# ProPrj___2026-02-20.net
KiCad netlist of a schematic drawn in EasyEDA Pro
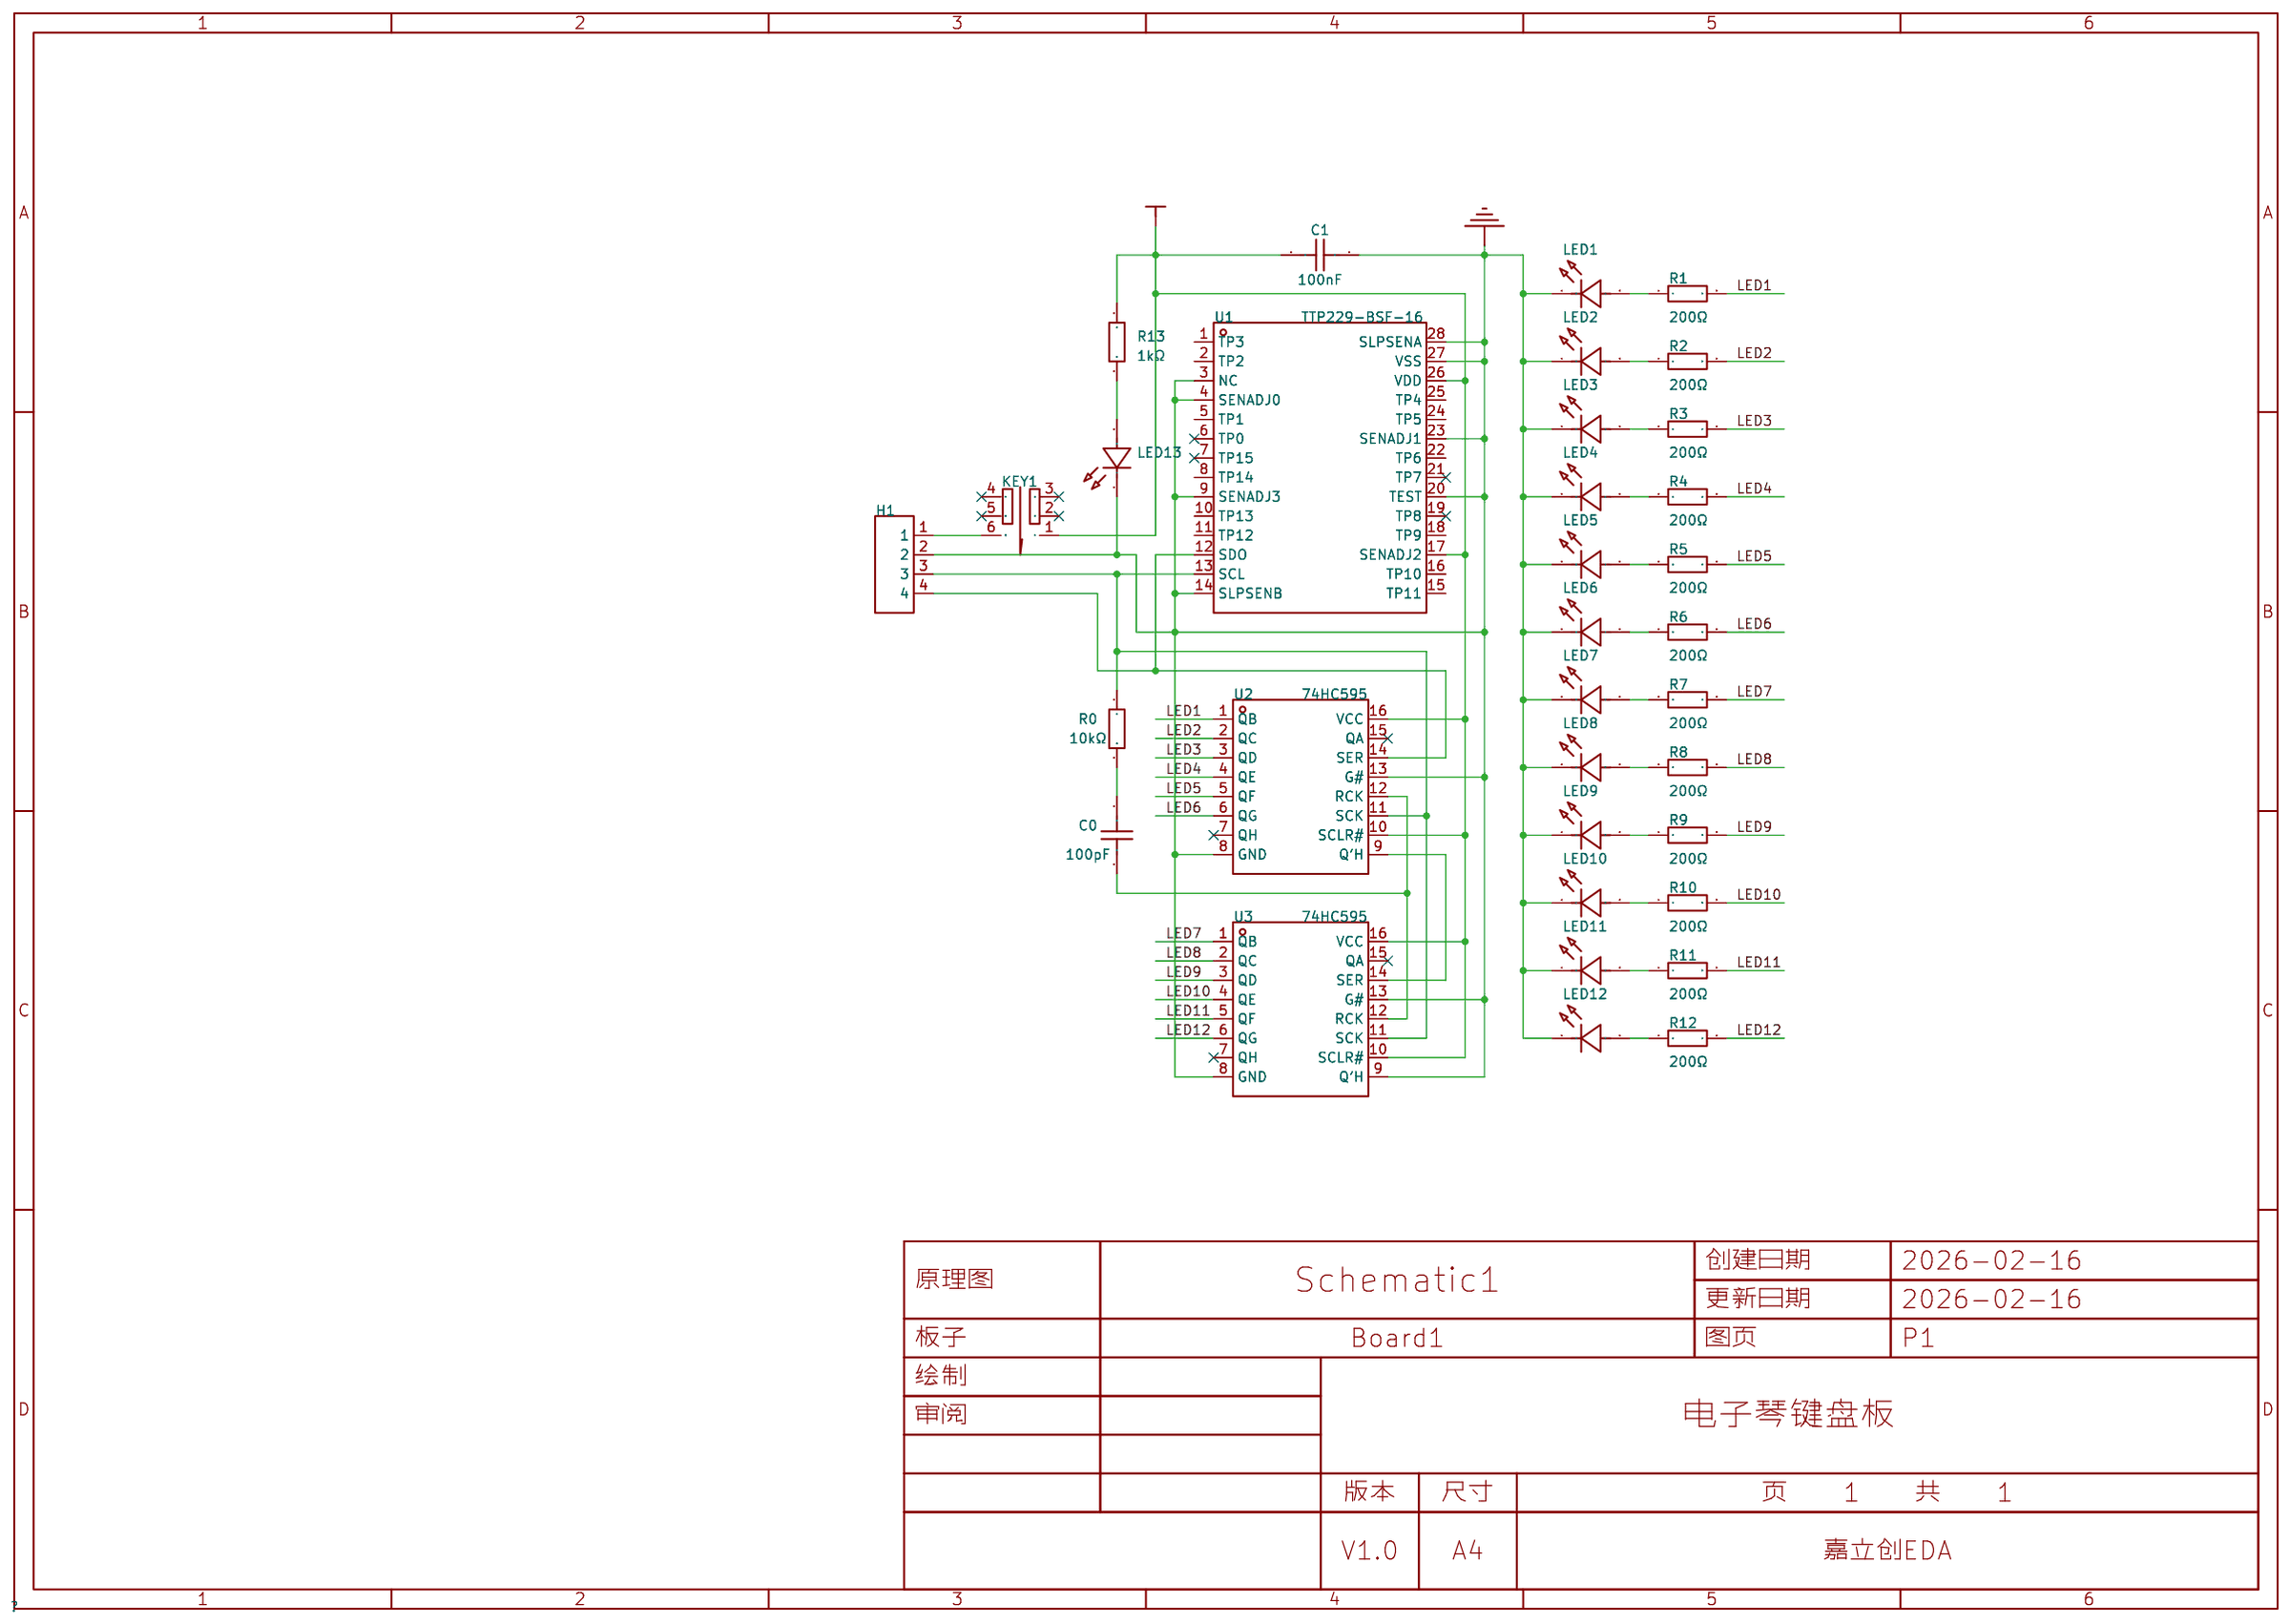
[diagram p0: schematic sheet]

(export (version "E")
  (design (tool "Eeschema 10.0.6"))
  (components
    (comp (ref "C0")
      (value "100pF")
      (footprint "easyedapro:C0603")
      (fields
        (field (name "Manufacturer Part") "CC0603JRNPO9BN101")
        (field (name "Manufacturer") "YAGEO(国巨)")
      )
      (libsource (lib "easyedapro") (part "CC0603JRNPO9BN101"))
    )
    (comp (ref "C1")
      (value "100nF")
      (footprint "easyedapro:C0603")
      (fields
        (field (name "Manufacturer Part") "CGA0603X7R104K500JT")
        (field (name "Manufacturer") "HRE(芯声)")
      )
      (libsource (lib "easyedapro") (part "CGA0603X7R104K500JT"))
    )
    (comp (ref "H1")
      (value "2.54-1*4")
      (footprint "easyedapro:HDR-TH_4P-P2.54-V-M-1")
      (fields (field (name "Manufacturer") "ZHOURI(洲日)"))
      (libsource (lib "easyedapro") (part "2.54-1*4"))
    )
    (comp (ref "KEY1")
      (value "自锁开关 5.8Z白灰白260G")
      (footprint "easyedapro:SW-TH_6P-L5.8-W5.8-P2.00-LS4.5-TR")
      (description "耐温260度")
      (libsource (lib "easyedapro") (part "Self-locking switch 5.8ZWhite and white260G"))
    )
    (comp (ref "LED1")
      (value "GL0603UB01")
      (footprint "easyedapro:LED0805-RD_GREEN")
      (fields (field (name "Manufacturer") "Guiguang light(桂光光电)"))
      (libsource (lib "easyedapro") (part "XL-2012UGC"))
    )
    (comp (ref "LED2")
      (value "GL0603UB01")
      (footprint "easyedapro:LED0805-RD_GREEN")
      (fields (field (name "Manufacturer") "Guiguang light(桂光光电)"))
      (libsource (lib "easyedapro") (part "XL-2012UGC"))
    )
    (comp (ref "LED3")
      (value "GL0603UB01")
      (footprint "easyedapro:LED0805-RD_GREEN")
      (fields (field (name "Manufacturer") "Guiguang light(桂光光电)"))
      (libsource (lib "easyedapro") (part "XL-2012UGC"))
    )
    (comp (ref "LED4")
      (value "GL0603UB01")
      (footprint "easyedapro:LED0805-RD_GREEN")
      (fields (field (name "Manufacturer") "Guiguang light(桂光光电)"))
      (libsource (lib "easyedapro") (part "XL-2012UGC"))
    )
    (comp (ref "LED5")
      (value "GL0603UB01")
      (footprint "easyedapro:LED0805-RD_GREEN")
      (fields (field (name "Manufacturer") "Guiguang light(桂光光电)"))
      (libsource (lib "easyedapro") (part "XL-2012UGC"))
    )
    (comp (ref "LED6")
      (value "GL0603UB01")
      (footprint "easyedapro:LED0805-RD_GREEN")
      (fields (field (name "Manufacturer") "Guiguang light(桂光光电)"))
      (libsource (lib "easyedapro") (part "XL-2012UGC"))
    )
    (comp (ref "LED7")
      (value "GL0603UB01")
      (footprint "easyedapro:LED0805-RD_GREEN")
      (fields (field (name "Manufacturer") "Guiguang light(桂光光电)"))
      (libsource (lib "easyedapro") (part "XL-2012UGC"))
    )
    (comp (ref "LED8")
      (value "GL0603UB01")
      (footprint "easyedapro:LED0805-RD_GREEN")
      (fields (field (name "Manufacturer") "Guiguang light(桂光光电)"))
      (libsource (lib "easyedapro") (part "XL-2012UGC"))
    )
    (comp (ref "LED9")
      (value "GL0603UB01")
      (footprint "easyedapro:LED0805-RD_GREEN")
      (fields (field (name "Manufacturer") "Guiguang light(桂光光电)"))
      (libsource (lib "easyedapro") (part "XL-2012UGC"))
    )
    (comp (ref "LED10")
      (value "GL0603UB01")
      (footprint "easyedapro:LED0805-RD_GREEN")
      (fields (field (name "Manufacturer") "Guiguang light(桂光光电)"))
      (libsource (lib "easyedapro") (part "XL-2012UGC"))
    )
    (comp (ref "LED11")
      (value "GL0603UB01")
      (footprint "easyedapro:LED0805-RD_GREEN")
      (fields (field (name "Manufacturer") "Guiguang light(桂光光电)"))
      (libsource (lib "easyedapro") (part "XL-2012UGC"))
    )
    (comp (ref "LED12")
      (value "GL0603UB01")
      (footprint "easyedapro:LED0805-RD_GREEN")
      (fields (field (name "Manufacturer") "Guiguang light(桂光光电)"))
      (libsource (lib "easyedapro") (part "XL-2012UGC"))
    )
    (comp (ref "LED13")
      (value "GL0603UB01")
      (footprint "easyedapro:LED0805-RD_GREEN")
      (fields (field (name "Manufacturer") "Guiguang light(桂光光电)"))
      (libsource (lib "easyedapro") (part "XL-2012UGC"))
    )
    (comp (ref "R0")
      (value "10kΩ")
      (footprint "easyedapro:R0805")
      (fields
        (field (name "Manufacturer Part") "0603WAF1002T5E")
        (field (name "Manufacturer") "UNI-ROYAL(厚声)")
      )
      (libsource (lib "easyedapro") (part "电阻"))
    )
    (comp (ref "R1")
      (value "200Ω")
      (footprint "easyedapro:R0805")
      (fields
        (field (name "Manufacturer Part") "0603WAF2000T5E")
        (field (name "Manufacturer") "UNI-ROYAL(厚声)")
      )
      (libsource (lib "easyedapro") (part "电阻"))
    )
    (comp (ref "R2")
      (value "200Ω")
      (footprint "easyedapro:R0805")
      (fields
        (field (name "Manufacturer Part") "0603WAF2000T5E")
        (field (name "Manufacturer") "UNI-ROYAL(厚声)")
      )
      (libsource (lib "easyedapro") (part "电阻"))
    )
    (comp (ref "R3")
      (value "200Ω")
      (footprint "easyedapro:R0805")
      (fields
        (field (name "Manufacturer Part") "0603WAF2000T5E")
        (field (name "Manufacturer") "UNI-ROYAL(厚声)")
      )
      (libsource (lib "easyedapro") (part "电阻"))
    )
    (comp (ref "R4")
      (value "200Ω")
      (footprint "easyedapro:R0805")
      (fields
        (field (name "Manufacturer Part") "0603WAF2000T5E")
        (field (name "Manufacturer") "UNI-ROYAL(厚声)")
      )
      (libsource (lib "easyedapro") (part "电阻"))
    )
    (comp (ref "R5")
      (value "200Ω")
      (footprint "easyedapro:R0805")
      (fields
        (field (name "Manufacturer Part") "0603WAF2000T5E")
        (field (name "Manufacturer") "UNI-ROYAL(厚声)")
      )
      (libsource (lib "easyedapro") (part "电阻"))
    )
    (comp (ref "R6")
      (value "200Ω")
      (footprint "easyedapro:R0805")
      (fields
        (field (name "Manufacturer Part") "0603WAF2000T5E")
        (field (name "Manufacturer") "UNI-ROYAL(厚声)")
      )
      (libsource (lib "easyedapro") (part "电阻"))
    )
    (comp (ref "R7")
      (value "200Ω")
      (footprint "easyedapro:R0805")
      (fields
        (field (name "Manufacturer Part") "0603WAF2000T5E")
        (field (name "Manufacturer") "UNI-ROYAL(厚声)")
      )
      (libsource (lib "easyedapro") (part "电阻"))
    )
    (comp (ref "R8")
      (value "200Ω")
      (footprint "easyedapro:R0805")
      (fields
        (field (name "Manufacturer Part") "0603WAF2000T5E")
        (field (name "Manufacturer") "UNI-ROYAL(厚声)")
      )
      (libsource (lib "easyedapro") (part "电阻"))
    )
    (comp (ref "R9")
      (value "200Ω")
      (footprint "easyedapro:R0805")
      (fields
        (field (name "Manufacturer Part") "0603WAF2000T5E")
        (field (name "Manufacturer") "UNI-ROYAL(厚声)")
      )
      (libsource (lib "easyedapro") (part "电阻"))
    )
    (comp (ref "R10")
      (value "200Ω")
      (footprint "easyedapro:R0805")
      (fields
        (field (name "Manufacturer Part") "0603WAF2000T5E")
        (field (name "Manufacturer") "UNI-ROYAL(厚声)")
      )
      (libsource (lib "easyedapro") (part "电阻"))
    )
    (comp (ref "R11")
      (value "200Ω")
      (footprint "easyedapro:R0805")
      (fields
        (field (name "Manufacturer Part") "0603WAF2000T5E")
        (field (name "Manufacturer") "UNI-ROYAL(厚声)")
      )
      (libsource (lib "easyedapro") (part "电阻"))
    )
    (comp (ref "R12")
      (value "200Ω")
      (footprint "easyedapro:R0805")
      (fields
        (field (name "Manufacturer Part") "0603WAF2000T5E")
        (field (name "Manufacturer") "UNI-ROYAL(厚声)")
      )
      (libsource (lib "easyedapro") (part "电阻"))
    )
    (comp (ref "R13")
      (value "1kΩ")
      (footprint "easyedapro:R0603")
      (description "电阻类型:厚膜电阻;阻值:1kΩ;精度:±1%;功率:100mW;工作电压:75V;温度系数:±100ppm/℃;")
      (fields (field (name "Manufacturer Part") "RC0603FR-071KL") (field (name "Manufacturer") "YAGEO(国巨)"))
      (libsource (lib "easyedapro") (part "RC0603FR-071KL"))
    )
    (comp (ref "U1")
      (value "TTP229-BSF-16")
      (footprint "easyedapro:SSOP-28_L9.9-W3.9-P0.64-LS6.0-BL")
      (fields (field (name "Manufacturer") "TONTEK(通泰)"))
      (libsource (lib "easyedapro") (part "TTP229-BSF-16"))
    )
    (comp (ref "U2")
      (value "74HC595")
      (footprint "easyedapro:SOP-16_L9.9-W3.9-P1.27-LS6.0-BL")
      (fields (field (name "Manufacturer") "GR(国睿)"))
      (libsource (lib "easyedapro") (part "74HC595"))
    )
    (comp (ref "U3")
      (value "74HC595")
      (footprint "easyedapro:SOP-16_L9.9-W3.9-P1.27-LS6.0-BL")
      (fields (field (name "Manufacturer") "GR(国睿)"))
      (libsource (lib "easyedapro") (part "74HC595"))
    )
  )
  (nets
    (net (code "1") (name "/LED1") (class "Default")
      (node (ref "R1") (pin "2") (pinfunction "2_2") (pintype "input"))
      (node (ref "U2") (pin "1") (pinfunction "QB_1") (pintype "unspecified"))
    )
    (net (code "2") (name "/LED2") (class "Default")
      (node (ref "R2") (pin "2") (pinfunction "2_2") (pintype "input"))
      (node (ref "U2") (pin "2") (pinfunction "QC_2") (pintype "unspecified"))
    )
    (net (code "3") (name "/LED3") (class "Default")
      (node (ref "R3") (pin "2") (pinfunction "2_2") (pintype "input"))
      (node (ref "U2") (pin "3") (pinfunction "QD_3") (pintype "unspecified"))
    )
    (net (code "4") (name "/LED4") (class "Default")
      (node (ref "R4") (pin "2") (pinfunction "2_2") (pintype "input"))
      (node (ref "U2") (pin "4") (pinfunction "QE_4") (pintype "unspecified"))
    )
    (net (code "5") (name "/LED5") (class "Default")
      (node (ref "R5") (pin "2") (pinfunction "2_2") (pintype "input"))
      (node (ref "U2") (pin "5") (pinfunction "QF_5") (pintype "unspecified"))
    )
    (net (code "6") (name "/LED6") (class "Default")
      (node (ref "R6") (pin "2") (pinfunction "2_2") (pintype "input"))
      (node (ref "U2") (pin "6") (pinfunction "QG_6") (pintype "unspecified"))
    )
    (net (code "7") (name "/LED7") (class "Default")
      (node (ref "R7") (pin "2") (pinfunction "2_2") (pintype "input"))
      (node (ref "U3") (pin "1") (pinfunction "QB_1") (pintype "unspecified"))
    )
    (net (code "8") (name "/LED8") (class "Default")
      (node (ref "R8") (pin "2") (pinfunction "2_2") (pintype "input"))
      (node (ref "U3") (pin "2") (pinfunction "QC_2") (pintype "unspecified"))
    )
    (net (code "9") (name "/LED9") (class "Default")
      (node (ref "R9") (pin "2") (pinfunction "2_2") (pintype "input"))
      (node (ref "U3") (pin "3") (pinfunction "QD_3") (pintype "unspecified"))
    )
    (net (code "10") (name "/LED10") (class "Default")
      (node (ref "R10") (pin "2") (pinfunction "2_2") (pintype "input"))
      (node (ref "U3") (pin "4") (pinfunction "QE_4") (pintype "unspecified"))
    )
    (net (code "11") (name "/LED11") (class "Default")
      (node (ref "R11") (pin "2") (pinfunction "2_2") (pintype "input"))
      (node (ref "U3") (pin "5") (pinfunction "QF_5") (pintype "unspecified"))
    )
    (net (code "12") (name "/LED12") (class "Default")
      (node (ref "R12") (pin "2") (pinfunction "2_2") (pintype "input"))
      (node (ref "U3") (pin "6") (pinfunction "QG_6") (pintype "unspecified"))
    )
    (net (code "13") (name "GND") (class "Default")
      (node (ref "C1") (pin "1") (pinfunction "1_1") (pintype "unspecified"))
      (node (ref "H1") (pin "2") (pinfunction "2_2") (pintype "unspecified"))
      (node (ref "LED1") (pin "1") (pinfunction "K_1") (pintype "unspecified"))
      (node (ref "LED10") (pin "1") (pinfunction "K_1") (pintype "unspecified"))
      (node (ref "LED11") (pin "1") (pinfunction "K_1") (pintype "unspecified"))
      (node (ref "LED12") (pin "1") (pinfunction "K_1") (pintype "unspecified"))
      (node (ref "LED13") (pin "1") (pinfunction "K_1") (pintype "unspecified"))
      (node (ref "LED2") (pin "1") (pinfunction "K_1") (pintype "unspecified"))
      (node (ref "LED3") (pin "1") (pinfunction "K_1") (pintype "unspecified"))
      (node (ref "LED4") (pin "1") (pinfunction "K_1") (pintype "unspecified"))
      (node (ref "LED5") (pin "1") (pinfunction "K_1") (pintype "unspecified"))
      (node (ref "LED6") (pin "1") (pinfunction "K_1") (pintype "unspecified"))
      (node (ref "LED7") (pin "1") (pinfunction "K_1") (pintype "unspecified"))
      (node (ref "LED8") (pin "1") (pinfunction "K_1") (pintype "unspecified"))
      (node (ref "LED9") (pin "1") (pinfunction "K_1") (pintype "unspecified"))
      (node (ref "U1") (pin "14") (pinfunction "SLPSENB_14") (pintype "unspecified"))
      (node (ref "U1") (pin "20") (pinfunction "TEST_20") (pintype "unspecified"))
      (node (ref "U1") (pin "23") (pinfunction "SENADJ1_23") (pintype "unspecified"))
      (node (ref "U1") (pin "27") (pinfunction "VSS_27") (pintype "unspecified"))
      (node (ref "U1") (pin "28") (pinfunction "SLPSENA_28") (pintype "unspecified"))
      (node (ref "U1") (pin "3") (pinfunction "NC_3") (pintype "unspecified"))
      (node (ref "U1") (pin "4") (pinfunction "SENADJ0_4") (pintype "unspecified"))
      (node (ref "U1") (pin "9") (pinfunction "SENADJ3_9") (pintype "unspecified"))
      (node (ref "U2") (pin "13") (pinfunction "G#_13") (pintype "unspecified"))
      (node (ref "U2") (pin "8") (pinfunction "GND_8") (pintype "unspecified"))
      (node (ref "U3") (pin "13") (pinfunction "G#_13") (pintype "unspecified"))
      (node (ref "U3") (pin "8") (pinfunction "GND_8") (pintype "unspecified"))
      (node (ref "U3") (pin "9") (pinfunction "Q′H_9") (pintype "unspecified"))
    )
    (net (code "14") (name "Net-(C0-Pad1)") (class "Default")
      (node (ref "C0") (pin "1") (pinfunction "1_1") (pintype "unspecified"))
      (node (ref "R0") (pin "2") (pinfunction "2_2") (pintype "input"))
    )
    (net (code "15") (name "Net-(H1-Pad1)") (class "Default")
      (node (ref "H1") (pin "1") (pinfunction "1_1") (pintype "unspecified"))
      (node (ref "KEY1") (pin "6") (pinfunction "6_6") (pintype "input"))
    )
    (net (code "16") (name "Net-(LED1-A)") (class "Default")
      (node (ref "LED1") (pin "2") (pinfunction "A_2") (pintype "unspecified"))
      (node (ref "R1") (pin "1") (pinfunction "1_1") (pintype "input"))
    )
    (net (code "17") (name "Net-(LED2-A)") (class "Default")
      (node (ref "LED2") (pin "2") (pinfunction "A_2") (pintype "unspecified"))
      (node (ref "R2") (pin "1") (pinfunction "1_1") (pintype "input"))
    )
    (net (code "18") (name "Net-(LED3-A)") (class "Default")
      (node (ref "LED3") (pin "2") (pinfunction "A_2") (pintype "unspecified"))
      (node (ref "R3") (pin "1") (pinfunction "1_1") (pintype "input"))
    )
    (net (code "19") (name "Net-(LED4-A)") (class "Default")
      (node (ref "LED4") (pin "2") (pinfunction "A_2") (pintype "unspecified"))
      (node (ref "R4") (pin "1") (pinfunction "1_1") (pintype "input"))
    )
    (net (code "20") (name "Net-(LED5-A)") (class "Default")
      (node (ref "LED5") (pin "2") (pinfunction "A_2") (pintype "unspecified"))
      (node (ref "R5") (pin "1") (pinfunction "1_1") (pintype "input"))
    )
    (net (code "21") (name "Net-(LED6-A)") (class "Default")
      (node (ref "LED6") (pin "2") (pinfunction "A_2") (pintype "unspecified"))
      (node (ref "R6") (pin "1") (pinfunction "1_1") (pintype "input"))
    )
    (net (code "22") (name "Net-(LED7-A)") (class "Default")
      (node (ref "LED7") (pin "2") (pinfunction "A_2") (pintype "unspecified"))
      (node (ref "R7") (pin "1") (pinfunction "1_1") (pintype "input"))
    )
    (net (code "23") (name "Net-(LED8-A)") (class "Default")
      (node (ref "LED8") (pin "2") (pinfunction "A_2") (pintype "unspecified"))
      (node (ref "R8") (pin "1") (pinfunction "1_1") (pintype "input"))
    )
    (net (code "24") (name "Net-(LED9-A)") (class "Default")
      (node (ref "LED9") (pin "2") (pinfunction "A_2") (pintype "unspecified"))
      (node (ref "R9") (pin "1") (pinfunction "1_1") (pintype "input"))
    )
    (net (code "25") (name "Net-(LED10-A)") (class "Default")
      (node (ref "LED10") (pin "2") (pinfunction "A_2") (pintype "unspecified"))
      (node (ref "R10") (pin "1") (pinfunction "1_1") (pintype "input"))
    )
    (net (code "26") (name "Net-(LED11-A)") (class "Default")
      (node (ref "LED11") (pin "2") (pinfunction "A_2") (pintype "unspecified"))
      (node (ref "R11") (pin "1") (pinfunction "1_1") (pintype "input"))
    )
    (net (code "27") (name "Net-(LED12-A)") (class "Default")
      (node (ref "LED12") (pin "2") (pinfunction "A_2") (pintype "unspecified"))
      (node (ref "R12") (pin "1") (pinfunction "1_1") (pintype "input"))
    )
    (net (code "28") (name "Net-(LED13-A)") (class "Default")
      (node (ref "LED13") (pin "2") (pinfunction "A_2") (pintype "unspecified"))
      (node (ref "R13") (pin "2") (pinfunction "2_2") (pintype "input"))
    )
    (net (code "29") (name "Net-(U1-SCL)") (class "Default")
      (node (ref "H1") (pin "3") (pinfunction "3_3") (pintype "unspecified"))
      (node (ref "R0") (pin "1") (pinfunction "1_1") (pintype "input"))
      (node (ref "U1") (pin "13") (pinfunction "SCL_13") (pintype "unspecified"))
      (node (ref "U2") (pin "11") (pinfunction "SCK_11") (pintype "unspecified"))
      (node (ref "U3") (pin "11") (pinfunction "SCK_11") (pintype "unspecified"))
    )
    (net (code "30") (name "Net-(U1-SDO)") (class "Default")
      (node (ref "H1") (pin "4") (pinfunction "4_4") (pintype "unspecified"))
      (node (ref "U1") (pin "12") (pinfunction "SDO_12") (pintype "unspecified"))
      (node (ref "U2") (pin "14") (pinfunction "SER_14") (pintype "unspecified"))
    )
    (net (code "31") (name "Net-(U2-Q′H)") (class "Default")
      (node (ref "U2") (pin "9") (pinfunction "Q′H_9") (pintype "unspecified"))
      (node (ref "U3") (pin "14") (pinfunction "SER_14") (pintype "unspecified"))
    )
    (net (code "32") (name "Net-(U2-RCK)") (class "Default")
      (node (ref "C0") (pin "2") (pinfunction "2_2") (pintype "unspecified"))
      (node (ref "U2") (pin "12") (pinfunction "RCK_12") (pintype "unspecified"))
      (node (ref "U3") (pin "12") (pinfunction "RCK_12") (pintype "unspecified"))
    )
    (net (code "33") (name "VCC") (class "Default")
      (node (ref "C1") (pin "2") (pinfunction "2_2") (pintype "unspecified"))
      (node (ref "KEY1") (pin "1") (pinfunction "1_1") (pintype "input"))
      (node (ref "R13") (pin "1") (pinfunction "1_1") (pintype "input"))
      (node (ref "U1") (pin "17") (pinfunction "SENADJ2_17") (pintype "unspecified"))
      (node (ref "U1") (pin "26") (pinfunction "VDD_26") (pintype "unspecified"))
      (node (ref "U2") (pin "10") (pinfunction "SCLR#_10") (pintype "unspecified"))
      (node (ref "U2") (pin "16") (pinfunction "VCC_16") (pintype "unspecified"))
      (node (ref "U3") (pin "10") (pinfunction "SCLR#_10") (pintype "unspecified"))
      (node (ref "U3") (pin "16") (pinfunction "VCC_16") (pintype "unspecified"))
    )
    (net (code "34") (name "unconnected-(KEY1-Pad2)") (class "Default")
      (node (ref "KEY1") (pin "2") (pinfunction "2_2") (pintype "input+no_connect"))
    )
    (net (code "35") (name "unconnected-(KEY1-Pad3)") (class "Default")
      (node (ref "KEY1") (pin "3") (pinfunction "3_3") (pintype "input+no_connect"))
    )
    (net (code "36") (name "unconnected-(KEY1-Pad4)") (class "Default")
      (node (ref "KEY1") (pin "4") (pinfunction "4_4") (pintype "input+no_connect"))
    )
    (net (code "37") (name "unconnected-(KEY1-Pad5)") (class "Default")
      (node (ref "KEY1") (pin "5") (pinfunction "5_5") (pintype "input+no_connect"))
    )
    (net (code "38") (name "unconnected-(U1-TP0-Pad6)") (class "Default")
      (node (ref "U1") (pin "6") (pinfunction "TP0_6") (pintype "unspecified+no_connect"))
    )
    (net (code "39") (name "unconnected-(U1-TP1-Pad5)") (class "Default")
      (node (ref "U1") (pin "5") (pinfunction "TP1_5") (pintype "unspecified"))
    )
    (net (code "40") (name "unconnected-(U1-TP2-Pad2)") (class "Default")
      (node (ref "U1") (pin "2") (pinfunction "TP2_2") (pintype "unspecified"))
    )
    (net (code "41") (name "unconnected-(U1-TP3-Pad1)") (class "Default")
      (node (ref "U1") (pin "1") (pinfunction "TP3_1") (pintype "unspecified"))
    )
    (net (code "42") (name "unconnected-(U1-TP4-Pad25)") (class "Default")
      (node (ref "U1") (pin "25") (pinfunction "TP4_25") (pintype "unspecified"))
    )
    (net (code "43") (name "unconnected-(U1-TP5-Pad24)") (class "Default")
      (node (ref "U1") (pin "24") (pinfunction "TP5_24") (pintype "unspecified"))
    )
    (net (code "44") (name "unconnected-(U1-TP6-Pad22)") (class "Default")
      (node (ref "U1") (pin "22") (pinfunction "TP6_22") (pintype "unspecified"))
    )
    (net (code "45") (name "unconnected-(U1-TP7-Pad21)") (class "Default")
      (node (ref "U1") (pin "21") (pinfunction "TP7_21") (pintype "unspecified+no_connect"))
    )
    (net (code "46") (name "unconnected-(U1-TP8-Pad19)") (class "Default")
      (node (ref "U1") (pin "19") (pinfunction "TP8_19") (pintype "unspecified+no_connect"))
    )
    (net (code "47") (name "unconnected-(U1-TP9-Pad18)") (class "Default")
      (node (ref "U1") (pin "18") (pinfunction "TP9_18") (pintype "unspecified"))
    )
    (net (code "48") (name "unconnected-(U1-TP10-Pad16)") (class "Default")
      (node (ref "U1") (pin "16") (pinfunction "TP10_16") (pintype "unspecified"))
    )
    (net (code "49") (name "unconnected-(U1-TP11-Pad15)") (class "Default")
      (node (ref "U1") (pin "15") (pinfunction "TP11_15") (pintype "unspecified"))
    )
    (net (code "50") (name "unconnected-(U1-TP12-Pad11)") (class "Default")
      (node (ref "U1") (pin "11") (pinfunction "TP12_11") (pintype "unspecified"))
    )
    (net (code "51") (name "unconnected-(U1-TP13-Pad10)") (class "Default")
      (node (ref "U1") (pin "10") (pinfunction "TP13_10") (pintype "unspecified"))
    )
    (net (code "52") (name "unconnected-(U1-TP14-Pad8)") (class "Default")
      (node (ref "U1") (pin "8") (pinfunction "TP14_8") (pintype "unspecified"))
    )
    (net (code "53") (name "unconnected-(U1-TP15-Pad7)") (class "Default")
      (node (ref "U1") (pin "7") (pinfunction "TP15_7") (pintype "unspecified+no_connect"))
    )
    (net (code "54") (name "unconnected-(U2-QA-Pad15)") (class "Default")
      (node (ref "U2") (pin "15") (pinfunction "QA_15") (pintype "unspecified+no_connect"))
    )
    (net (code "55") (name "unconnected-(U2-QH-Pad7)") (class "Default")
      (node (ref "U2") (pin "7") (pinfunction "QH_7") (pintype "unspecified+no_connect"))
    )
    (net (code "56") (name "unconnected-(U3-QA-Pad15)") (class "Default")
      (node (ref "U3") (pin "15") (pinfunction "QA_15") (pintype "unspecified+no_connect"))
    )
    (net (code "57") (name "unconnected-(U3-QH-Pad7)") (class "Default")
      (node (ref "U3") (pin "7") (pinfunction "QH_7") (pintype "unspecified+no_connect"))
    )
  )
)
